# 20191228.net
KiCad netlist of a schematic drawn in Altium Designer
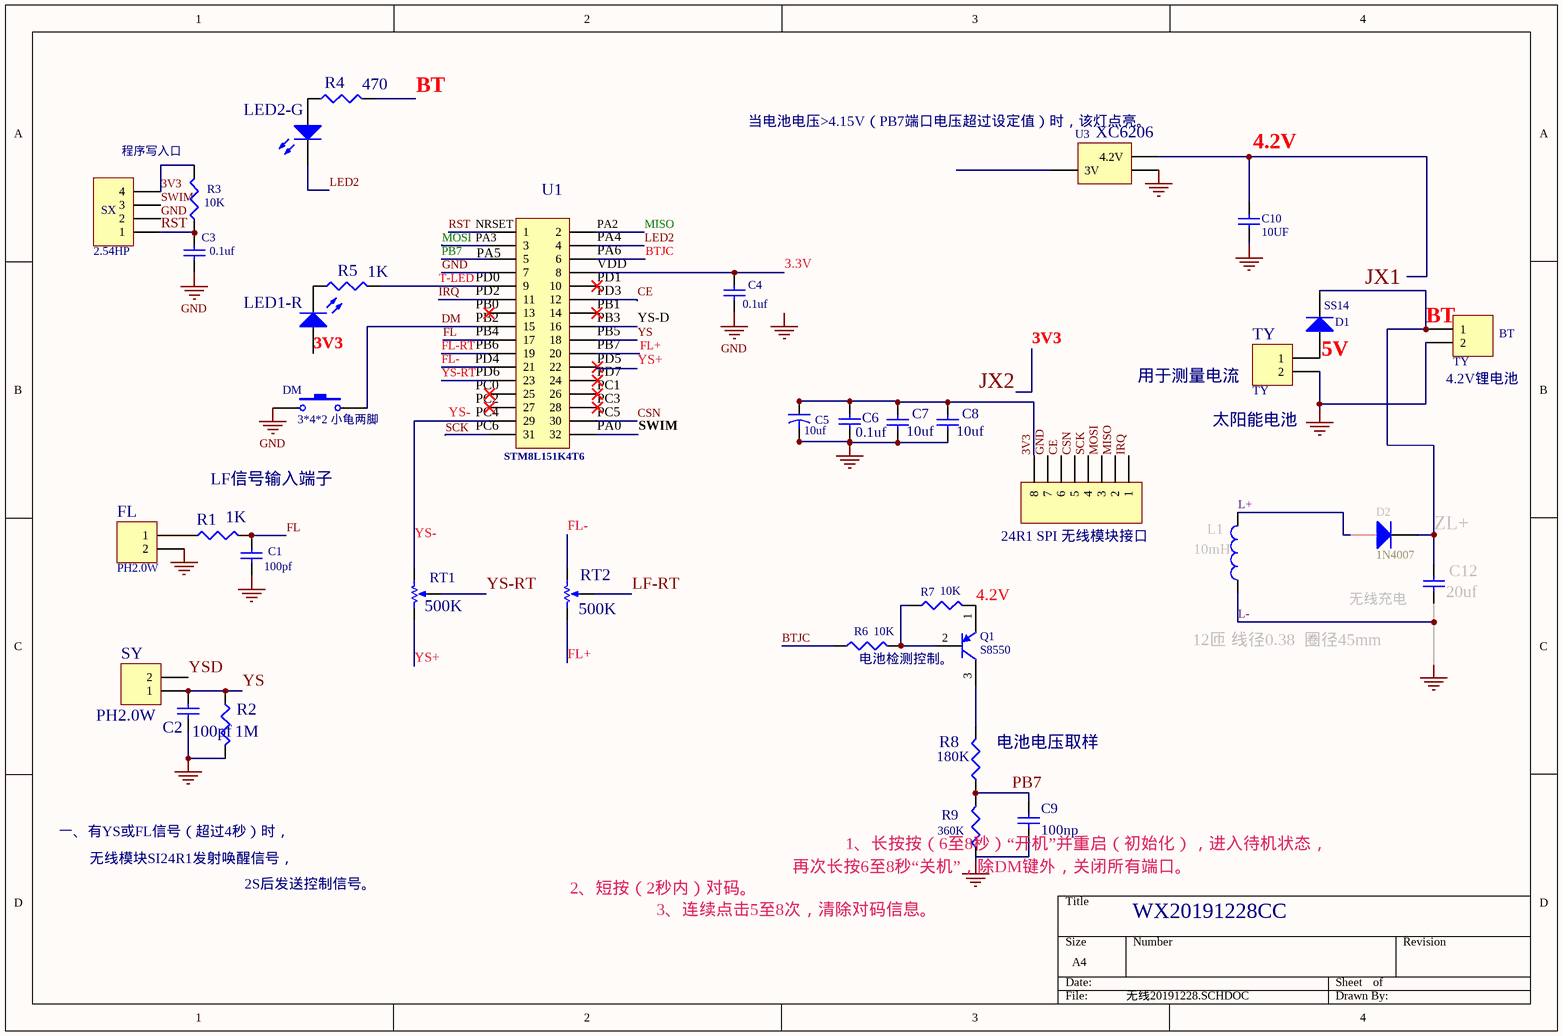
[diagram p0: 无线20191228.SCHDOC]

(export (version "E")
  (design (tool "Eeschema 10.0.6"))
  (components
    (comp (ref "24R1 SPI 无线模块接口")
      (value "Header 8")
      (footprint "HDR1X8")
      (description "Header, 8-Pin")
      (fields (field (name "PUBLISHER") "Altium Limited"))
      (libsource (lib "Miscellaneous Connectors") (part "Header 8"))
    )
    (comp (ref "BT")
      (value "TY")
      (footprint "HDR1X2")
      (description "Header, 2-Pin")
      (fields (field (name "PUBLISHER") "Altium Limited"))
      (libsource (lib "") (part "Header 2_2"))
    )
    (comp (ref "C1")
      (value "100pf")
      (footprint "CC1608-0603")
      (description "Capacitor (Semiconductor SIM Model)")
      (fields (field (name "PUBLISHER") "Altium Limited"))
      (libsource (lib "Miscellaneous Devices") (part "Cap Semi"))
    )
    (comp (ref "C2")
      (value "100pf")
      (footprint "CC1608-0603")
      (description "Capacitor (Semiconductor SIM Model)")
      (fields (field (name "PUBLISHER") "Altium Limited"))
      (libsource (lib "Miscellaneous Devices") (part "Cap Semi"))
    )
    (comp (ref "C3")
      (value "0.1uf")
      (footprint "CC1608-0603")
      (description "Capacitor (Semiconductor SIM Model)")
      (fields (field (name "Comment") "Cap Semi") (field (name "PUBLISHER") "Altium Limited"))
      (libsource (lib "Miscellaneous Devices") (part "Cap Semi"))
    )
    (comp (ref "C4")
      (value "0.1uf")
      (footprint "CC1608-0603")
      (description "Capacitor (Semiconductor SIM Model)")
      (fields (field (name "PUBLISHER") "Altium Limited"))
      (libsource (lib "Miscellaneous Devices") (part "Cap Semi"))
    )
    (comp (ref "C5")
      (value "10uf")
      (footprint "CAPPR2-5x6.8")
      (description "Capacitor")
      (fields (field (name "PUBLISHER") "Altium Limited"))
      (libsource (lib "Miscellaneous Devices") (part "Cap2"))
    )
    (comp (ref "C6")
      (value "0.1uf")
      (footprint "CC1608-0603")
      (description "Capacitor (Semiconductor SIM Model)")
      (fields (field (name "PUBLISHER") "Altium Limited"))
      (libsource (lib "Miscellaneous Devices") (part "Cap Semi"))
    )
    (comp (ref "C7")
      (value "10uf")
      (footprint "CC1608-0603")
      (description "Capacitor (Semiconductor SIM Model)")
      (fields (field (name "PUBLISHER") "Altium Limited"))
      (libsource (lib "Miscellaneous Devices") (part "Cap Semi"))
    )
    (comp (ref "C8")
      (value "10uf")
      (footprint "CC1608-0603")
      (description "Capacitor (Semiconductor SIM Model)")
      (fields (field (name "PUBLISHER") "Altium Limited"))
      (libsource (lib "Miscellaneous Devices") (part "Cap Semi"))
    )
    (comp (ref "C9")
      (value "100np")
      (footprint "CC1608-0603")
      (description "Capacitor (Semiconductor SIM Model)")
      (fields (field (name "PUBLISHER") "Altium Limited"))
      (libsource (lib "Miscellaneous Devices") (part "Cap Semi"))
    )
    (comp (ref "C10")
      (value "10UF")
      (footprint "CC1608-0603")
      (description "Capacitor (Semiconductor SIM Model)")
      (fields (field (name "PUBLISHER") "Altium Limited"))
      (libsource (lib "Miscellaneous Devices") (part "Cap Semi"))
    )
    (comp (ref "C12")
      (value "20uf")
      (footprint "CC1608-0603")
      (description "Capacitor (Semiconductor SIM Model)")
      (fields (field (name "PUBLISHER") "Altium Limited"))
      (libsource (lib "Miscellaneous Devices") (part "Cap Semi"))
    )
    (comp (ref "D1")
      (value "SS14")
      (footprint "DIO7.1-3.9x1.9")
      (description "High Conductance Fast Diode")
      (fields (field (name "PUBLISHER") "Altium Limited"))
      (libsource (lib "Miscellaneous Devices") (part "Diode 1N4148"))
    )
    (comp (ref "D2")
      (value "1N4007")
      (footprint "DIO7.1-3.9x1.9")
      (description "High Conductance Fast Diode")
      (fields (field (name "PUBLISHER") "Altium Limited"))
      (libsource (lib "Miscellaneous Devices") (part "Diode 1N4148"))
    )
    (comp (ref "DM")
      (value "3*4*2 小龟两脚")
      (footprint "SPST-2")
      (description "Switch")
      (fields (field (name "PUBLISHER") "Altium Limited"))
      (libsource (lib "Miscellaneous Devices") (part "SW-PB"))
    )
    (comp (ref "FL")
      (value "PH2.0W")
      (footprint "HDR1X2")
      (description "Header, 2-Pin")
      (fields (field (name "PUBLISHER") "Altium Limited"))
      (libsource (lib "Miscellaneous Connectors") (part "Header 2"))
    )
    (comp (ref "L1")
      (value "12匝 线径0.38  圈径45mm")
      (footprint "INDC1005-0402")
      (description "Inductor")
      (fields (field (name "ALTIUM_VALUE") "10mH") (field (name "PUBLISHER") "Altium Limited"))
      (libsource (lib "Miscellaneous Devices") (part "Inductor"))
    )
    (comp (ref "LED1-R")
      (value "~")
      (footprint "LED-0")
      (description "Typical INFRARED GaAs LED")
      (fields (field (name "PUBLISHER") "Altium Limited"))
      (libsource (lib "Miscellaneous Devices") (part "LED0"))
    )
    (comp (ref "LED2-G")
      (value "~")
      (footprint "LED-0")
      (description "Typical INFRARED GaAs LED")
      (fields (field (name "PUBLISHER") "Altium Limited"))
      (libsource (lib "Miscellaneous Devices") (part "LED0"))
    )
    (comp (ref "Q1")
      (value "S8550")
      (footprint "BCY-W3/E4")
      (description "PNP General Purpose Amplifier")
      (fields (field (name "PUBLISHER") "Altium Limited"))
      (libsource (lib "MiscellaneousDevices2004") (part "2N3906"))
    )
    (comp (ref "R1")
      (value "1K")
      (footprint "C1608-0603")
      (description "Resistor")
      (fields (field (name "PUBLISHER") "Altium Limited"))
      (libsource (lib "Miscellaneous Devices") (part "Res3"))
    )
    (comp (ref "R2")
      (value "1M")
      (footprint "C1608-0603")
      (description "Resistor")
      (fields (field (name "PUBLISHER") "Altium Limited"))
      (libsource (lib "Miscellaneous Devices") (part "Res3"))
    )
    (comp (ref "R3")
      (value "10K")
      (footprint "C1608-0603")
      (description "Resistor")
      (fields (field (name "PUBLISHER") "Altium Limited"))
      (libsource (lib "Miscellaneous Devices") (part "Res3"))
    )
    (comp (ref "R4")
      (value "470")
      (footprint "C1608-0603")
      (description "Resistor")
      (fields (field (name "PUBLISHER") "Altium Limited"))
      (libsource (lib "Miscellaneous Devices") (part "Res3"))
    )
    (comp (ref "R5")
      (value "1K")
      (footprint "C1608-0603")
      (description "Resistor")
      (fields (field (name "PUBLISHER") "Altium Limited"))
      (libsource (lib "Miscellaneous Devices") (part "Res3"))
    )
    (comp (ref "R6")
      (value "10K")
      (footprint "C1608-0603")
      (description "Resistor")
      (fields (field (name "PUBLISHER") "Altium Limited"))
      (libsource (lib "Miscellaneous Devices") (part "Res3"))
    )
    (comp (ref "R7")
      (value "10K")
      (footprint "C1608-0603")
      (description "Resistor")
      (fields (field (name "PUBLISHER") "Altium Limited"))
      (libsource (lib "Miscellaneous Devices") (part "Res3"))
    )
    (comp (ref "R8")
      (value "180K")
      (footprint "C1608-0603")
      (description "Resistor")
      (fields (field (name "PUBLISHER") "Altium Limited"))
      (libsource (lib "Miscellaneous Devices") (part "Res3"))
    )
    (comp (ref "R9")
      (value "360K")
      (footprint "C1608-0603")
      (description "Resistor")
      (fields (field (name "PUBLISHER") "Altium Limited"))
      (libsource (lib "Miscellaneous Devices") (part "Res3"))
    )
    (comp (ref "RT1")
      (value "500K")
      (footprint "VR5")
      (description "Potentiometer")
      (fields (field (name "PUBLISHER") "Altium Limited"))
      (libsource (lib "Miscellaneous Devices") (part "RPot"))
    )
    (comp (ref "RT2")
      (value "500K")
      (footprint "VR5")
      (description "Potentiometer")
      (fields (field (name "PUBLISHER") "Altium Limited"))
      (libsource (lib "Miscellaneous Devices") (part "RPot"))
    )
    (comp (ref "SX")
      (value "2.54HP")
      (footprint "HDR1X4")
      (description "Header, 4-Pin")
      (fields (field (name "PUBLISHER") "Altium Limited"))
      (libsource (lib "Miscellaneous Connectors") (part "Header 4"))
    )
    (comp (ref "SY")
      (value "PH2.0W")
      (footprint "HDR1X2")
      (description "Header, 2-Pin")
      (fields (field (name "PUBLISHER") "Altium Limited"))
      (libsource (lib "") (part "Header 2_1"))
    )
    (comp (ref "TY")
      (value "TY")
      (footprint "HDR1X2")
      (description "Header, 2-Pin")
      (fields (field (name "PUBLISHER") "Altium Limited"))
      (libsource (lib "Miscellaneous Connectors") (part "Header 2"))
    )
    (comp (ref "U1")
      (value "STM8L151K4T6")
      (footprint "HDR2X16")
      (description "Header, 16-Pin, Dual row")
      (fields (field (name "PUBLISHER") "Altium Limited"))
      (libsource (lib "Miscellaneous Connectors") (part "Header 16X2"))
    )
    (comp (ref "U3")
      (value "XC6206")
      (footprint "MHDR2X2")
      (description "Header, 2-Pin, Dual row")
      (fields (field (name "PUBLISHER") "Altium Limited"))
      (libsource (lib "Miscellaneous Connectors") (part "MHDR2X2"))
    )
  )
  (nets
    (net (code "1") (name "/3.3V") (class "Default")
      (node (ref "C4") (pin "2") (pinfunction "2_2") (pintype "passive"))
      (node (ref "U1") (pin "8") (pinfunction "8_8") (pintype "passive"))
    )
    (net (code "2") (name "/3V3") (class "Default")
      (node (ref "24R1 SPI 无线模块接口") (pin "8") (pinfunction "8_8") (pintype "passive"))
      (node (ref "LED1-R") (pin "1") (pinfunction "A_1") (pintype "passive"))
      (node (ref "R3") (pin "2") (pinfunction "2_2") (pintype "passive"))
      (node (ref "SX") (pin "4") (pinfunction "4_4") (pintype "passive"))
    )
    (net (code "3") (name "/4.2V") (class "Default")
      (node (ref "Q1") (pin "1") (pinfunction "E_1") (pintype "passive"))
      (node (ref "R7") (pin "1") (pinfunction "1_1") (pintype "passive"))
    )
    (net (code "5") (name "/BT") (class "Default")
      (node (ref "BT") (pin "1") (pinfunction "1_1") (pintype "passive"))
      (node (ref "C12") (pin "1") (pinfunction "1_1") (pintype "passive"))
      (node (ref "D1") (pin "2") (pinfunction "K_2") (pintype "passive"))
      (node (ref "D2") (pin "2") (pinfunction "K_2") (pintype "passive"))
      (node (ref "R4") (pin "2") (pinfunction "2_2") (pintype "passive"))
    )
    (net (code "6") (name "/BTJC") (class "Default")
      (node (ref "R6") (pin "2") (pinfunction "2_2") (pintype "passive"))
      (node (ref "U1") (pin "6") (pinfunction "6_6") (pintype "passive"))
    )
    (net (code "7") (name "/CE") (class "Default")
      (node (ref "24R1 SPI 无线模块接口") (pin "6") (pinfunction "6_6") (pintype "passive"))
      (node (ref "U1") (pin "12") (pinfunction "12_12") (pintype "passive"))
    )
    (net (code "8") (name "/CSN") (class "Default")
      (node (ref "24R1 SPI 无线模块接口") (pin "5") (pinfunction "5_5") (pintype "passive"))
      (node (ref "U1") (pin "30") (pinfunction "30_30") (pintype "passive"))
    )
    (net (code "9") (name "/DM") (class "Default")
      (node (ref "DM") (pin "2") (pinfunction "2_2") (pintype "passive"))
      (node (ref "U1") (pin "15") (pinfunction "15_15") (pintype "passive"))
    )
    (net (code "10") (name "/FL") (class "Default")
      (node (ref "C1") (pin "2") (pinfunction "2_2") (pintype "passive"))
      (node (ref "R1") (pin "1") (pinfunction "1_1") (pintype "passive"))
      (node (ref "U1") (pin "17") (pinfunction "17_17") (pintype "passive"))
    )
    (net (code "11") (name "/FL+") (class "Default")
      (node (ref "RT2") (pin "2") (pinfunction "BOT_2") (pintype "passive"))
      (node (ref "U1") (pin "20") (pinfunction "20_20") (pintype "passive"))
    )
    (net (code "12") (name "/FL-") (class "Default")
      (node (ref "RT2") (pin "1") (pinfunction "TOP_1") (pintype "passive"))
      (node (ref "U1") (pin "21") (pinfunction "21_21") (pintype "passive"))
    )
    (net (code "13") (name "/FL-RT") (class "Default")
      (node (ref "U1") (pin "19") (pinfunction "19_19") (pintype "passive"))
    )
    (net (code "14") (name "/IRQ") (class "Default")
      (node (ref "24R1 SPI 无线模块接口") (pin "1") (pinfunction "1_1") (pintype "passive"))
      (node (ref "U1") (pin "11") (pinfunction "11_11") (pintype "passive"))
    )
    (net (code "16") (name "/L+") (class "Default")
      (node (ref "D2") (pin "1") (pinfunction "A_1") (pintype "passive"))
      (node (ref "L1") (pin "1") (pinfunction "1_1") (pintype "passive"))
    )
    (net (code "17") (name "/LED2") (class "Default")
      (node (ref "LED2-G") (pin "2") (pinfunction "K_2") (pintype "passive"))
      (node (ref "U1") (pin "4") (pinfunction "4_4") (pintype "passive"))
    )
    (net (code "18") (name "/LF-RT") (class "Default")
      (node (ref "RT2") (pin "3") (pinfunction "TAP_3") (pintype "passive"))
    )
    (net (code "19") (name "/MISO") (class "Default")
      (node (ref "24R1 SPI 无线模块接口") (pin "2") (pinfunction "2_2") (pintype "passive"))
      (node (ref "U1") (pin "2") (pinfunction "2_2") (pintype "passive"))
    )
    (net (code "20") (name "/MOSI") (class "Default")
      (node (ref "24R1 SPI 无线模块接口") (pin "3") (pinfunction "3_3") (pintype "passive"))
      (node (ref "U1") (pin "3") (pinfunction "3_3") (pintype "passive"))
    )
    (net (code "21") (name "/NRSET") (class "Default")
      (node (ref "C3") (pin "2") (pinfunction "2_2") (pintype "passive"))
      (node (ref "R3") (pin "1") (pinfunction "1_1") (pintype "passive"))
      (node (ref "SX") (pin "1") (pinfunction "1_1") (pintype "passive"))
      (node (ref "U1") (pin "1") (pinfunction "1_1") (pintype "passive"))
    )
    (net (code "22") (name "/PB7") (class "Default")
      (node (ref "C9") (pin "2") (pinfunction "2_2") (pintype "passive"))
      (node (ref "R8") (pin "1") (pinfunction "1_1") (pintype "passive"))
      (node (ref "R9") (pin "2") (pinfunction "2_2") (pintype "passive"))
      (node (ref "U1") (pin "5") (pinfunction "5_5") (pintype "passive"))
    )
    (net (code "23") (name "/SCK") (class "Default")
      (node (ref "24R1 SPI 无线模块接口") (pin "4") (pinfunction "4_4") (pintype "passive"))
      (node (ref "U1") (pin "31") (pinfunction "31_31") (pintype "passive"))
    )
    (net (code "24") (name "/SWIM") (class "Default")
      (node (ref "SX") (pin "3") (pinfunction "3_3") (pintype "passive"))
      (node (ref "U1") (pin "32") (pinfunction "32_32") (pintype "passive"))
    )
    (net (code "25") (name "/T-LED") (class "Default")
      (node (ref "R5") (pin "2") (pinfunction "2_2") (pintype "passive"))
      (node (ref "U1") (pin "9") (pinfunction "9_9") (pintype "passive"))
    )
    (net (code "26") (name "/YS") (class "Default")
      (node (ref "C2") (pin "2") (pinfunction "2_2") (pintype "passive"))
      (node (ref "R2") (pin "2") (pinfunction "2_2") (pintype "passive"))
      (node (ref "SY") (pin "1") (pinfunction "1_1") (pintype "passive"))
      (node (ref "U1") (pin "18") (pinfunction "18_18") (pintype "passive"))
    )
    (net (code "27") (name "/YS+") (class "Default")
      (node (ref "RT1") (pin "2") (pinfunction "BOT_2") (pintype "passive"))
      (node (ref "U1") (pin "22") (pinfunction "22_22") (pintype "passive"))
    )
    (net (code "28") (name "/YS-") (class "Default")
      (node (ref "RT1") (pin "1") (pinfunction "TOP_1") (pintype "passive"))
      (node (ref "U1") (pin "29") (pinfunction "29_29") (pintype "passive"))
    )
    (net (code "29") (name "/YS-D") (class "Default")
      (node (ref "U1") (pin "16") (pinfunction "16_16") (pintype "passive"))
    )
    (net (code "30") (name "/YS-RT") (class "Default")
      (node (ref "RT1") (pin "3") (pinfunction "TAP_3") (pintype "passive"))
      (node (ref "U1") (pin "23") (pinfunction "23_23") (pintype "passive"))
    )
    (net (code "31") (name "/YSD") (class "Default")
      (node (ref "SY") (pin "2") (pinfunction "2_2") (pintype "passive"))
    )
    (net (code "32") (name "GND") (class "Default")
      (node (ref "24R1 SPI 无线模块接口") (pin "7") (pinfunction "7_7") (pintype "passive"))
      (node (ref "BT") (pin "2") (pinfunction "2_2") (pintype "passive"))
      (node (ref "C1") (pin "1") (pinfunction "1_1") (pintype "passive"))
      (node (ref "C10") (pin "2") (pinfunction "2_2") (pintype "passive"))
      (node (ref "C12") (pin "2") (pinfunction "2_2") (pintype "passive"))
      (node (ref "C2") (pin "1") (pinfunction "1_1") (pintype "passive"))
      (node (ref "C3") (pin "1") (pinfunction "1_1") (pintype "passive"))
      (node (ref "C4") (pin "1") (pinfunction "1_1") (pintype "passive"))
      (node (ref "C5") (pin "2") (pinfunction "2_2") (pintype "passive"))
      (node (ref "C6") (pin "1") (pinfunction "1_1") (pintype "passive"))
      (node (ref "C7") (pin "1") (pinfunction "1_1") (pintype "passive"))
      (node (ref "C8") (pin "1") (pinfunction "1_1") (pintype "passive"))
      (node (ref "C9") (pin "1") (pinfunction "1_1") (pintype "passive"))
      (node (ref "DM") (pin "1") (pinfunction "1_1") (pintype "passive"))
      (node (ref "FL") (pin "2") (pinfunction "2_2") (pintype "passive"))
      (node (ref "L1") (pin "2") (pinfunction "2_2") (pintype "passive"))
      (node (ref "R2") (pin "1") (pinfunction "1_1") (pintype "passive"))
      (node (ref "R9") (pin "1") (pinfunction "1_1") (pintype "passive"))
      (node (ref "SX") (pin "2") (pinfunction "2_2") (pintype "passive"))
      (node (ref "TY") (pin "2") (pinfunction "2_2") (pintype "passive"))
      (node (ref "U1") (pin "7") (pinfunction "7_7") (pintype "passive"))
      (node (ref "U3") (pin "3.3OUT") (pintype "passive"))
    )
    (net (code "33") (name "Net-(C5-Pad1)") (class "Default")
      (node (ref "C5") (pin "1") (pinfunction "1_1") (pintype "passive"))
      (node (ref "C6") (pin "2") (pinfunction "2_2") (pintype "passive"))
      (node (ref "C7") (pin "2") (pinfunction "2_2") (pintype "passive"))
      (node (ref "C8") (pin "2") (pinfunction "2_2") (pintype "passive"))
    )
    (net (code "34") (name "Net-(D1-A)") (class "Default")
      (node (ref "D1") (pin "1") (pinfunction "A_1") (pintype "passive"))
      (node (ref "TY") (pin "1") (pinfunction "1_1") (pintype "passive"))
    )
    (net (code "35") (name "Net-(FL-Pad1)") (class "Default")
      (node (ref "FL") (pin "1") (pinfunction "1_1") (pintype "passive"))
      (node (ref "R1") (pin "2") (pinfunction "2_2") (pintype "passive"))
    )
    (net (code "36") (name "Net-(LED1-R-K)") (class "Default")
      (node (ref "LED1-R") (pin "2") (pinfunction "K_2") (pintype "passive"))
      (node (ref "R5") (pin "1") (pinfunction "1_1") (pintype "passive"))
    )
    (net (code "37") (name "Net-(LED2-G-A)") (class "Default")
      (node (ref "LED2-G") (pin "1") (pinfunction "A_1") (pintype "passive"))
      (node (ref "R4") (pin "1") (pinfunction "1_1") (pintype "passive"))
    )
    (net (code "38") (name "Net-(Q1-B)") (class "Default")
      (node (ref "Q1") (pin "2") (pinfunction "B_2") (pintype "passive"))
      (node (ref "R6") (pin "1") (pinfunction "1_1") (pintype "passive"))
      (node (ref "R7") (pin "2") (pinfunction "2_2") (pintype "passive"))
    )
    (net (code "39") (name "Net-(Q1-C)") (class "Default")
      (node (ref "Q1") (pin "3") (pinfunction "C_3") (pintype "passive"))
      (node (ref "R8") (pin "2") (pinfunction "2_2") (pintype "passive"))
    )
    (net (code "40") (name "Net-(U3-4.2V)") (class "Default")
      (node (ref "C10") (pin "1") (pinfunction "1_1") (pintype "passive"))
      (node (ref "U3") (pin "3.3_IN") (pinfunction "4.2V_3.3_IN") (pintype "passive"))
    )
    (net (code "41") (name "unconnected-(U1-Pad10)") (class "Default")
      (node (ref "U1") (pin "10") (pinfunction "10_10") (pintype "passive+no_connect"))
    )
    (net (code "42") (name "unconnected-(U1-Pad13)") (class "Default")
      (node (ref "U1") (pin "13") (pinfunction "13_13") (pintype "passive+no_connect"))
    )
    (net (code "43") (name "unconnected-(U1-Pad14)") (class "Default")
      (node (ref "U1") (pin "14") (pinfunction "14_14") (pintype "passive+no_connect"))
    )
    (net (code "44") (name "unconnected-(U1-Pad24)") (class "Default")
      (node (ref "U1") (pin "24") (pinfunction "24_24") (pintype "passive"))
    )
    (net (code "45") (name "unconnected-(U1-Pad25)") (class "Default")
      (node (ref "U1") (pin "25") (pinfunction "25_25") (pintype "passive"))
    )
    (net (code "46") (name "unconnected-(U1-Pad26)") (class "Default")
      (node (ref "U1") (pin "26") (pinfunction "26_26") (pintype "passive"))
    )
    (net (code "47") (name "unconnected-(U1-Pad27)") (class "Default")
      (node (ref "U1") (pin "27") (pinfunction "27_27") (pintype "passive"))
    )
    (net (code "48") (name "unconnected-(U1-Pad28)") (class "Default")
      (node (ref "U1") (pin "28") (pinfunction "28_28") (pintype "passive"))
    )
    (net (code "49") (name "unconnected-(U3-3V-Pad2)") (class "Default")
      (node (ref "U3") (pin "2") (pinfunction "3V_2") (pintype "passive"))
    )
  )
)
